# 10_-LPDDR4_SDRAM-2.net
KiCad netlist of a schematic drawn in Altium Designer
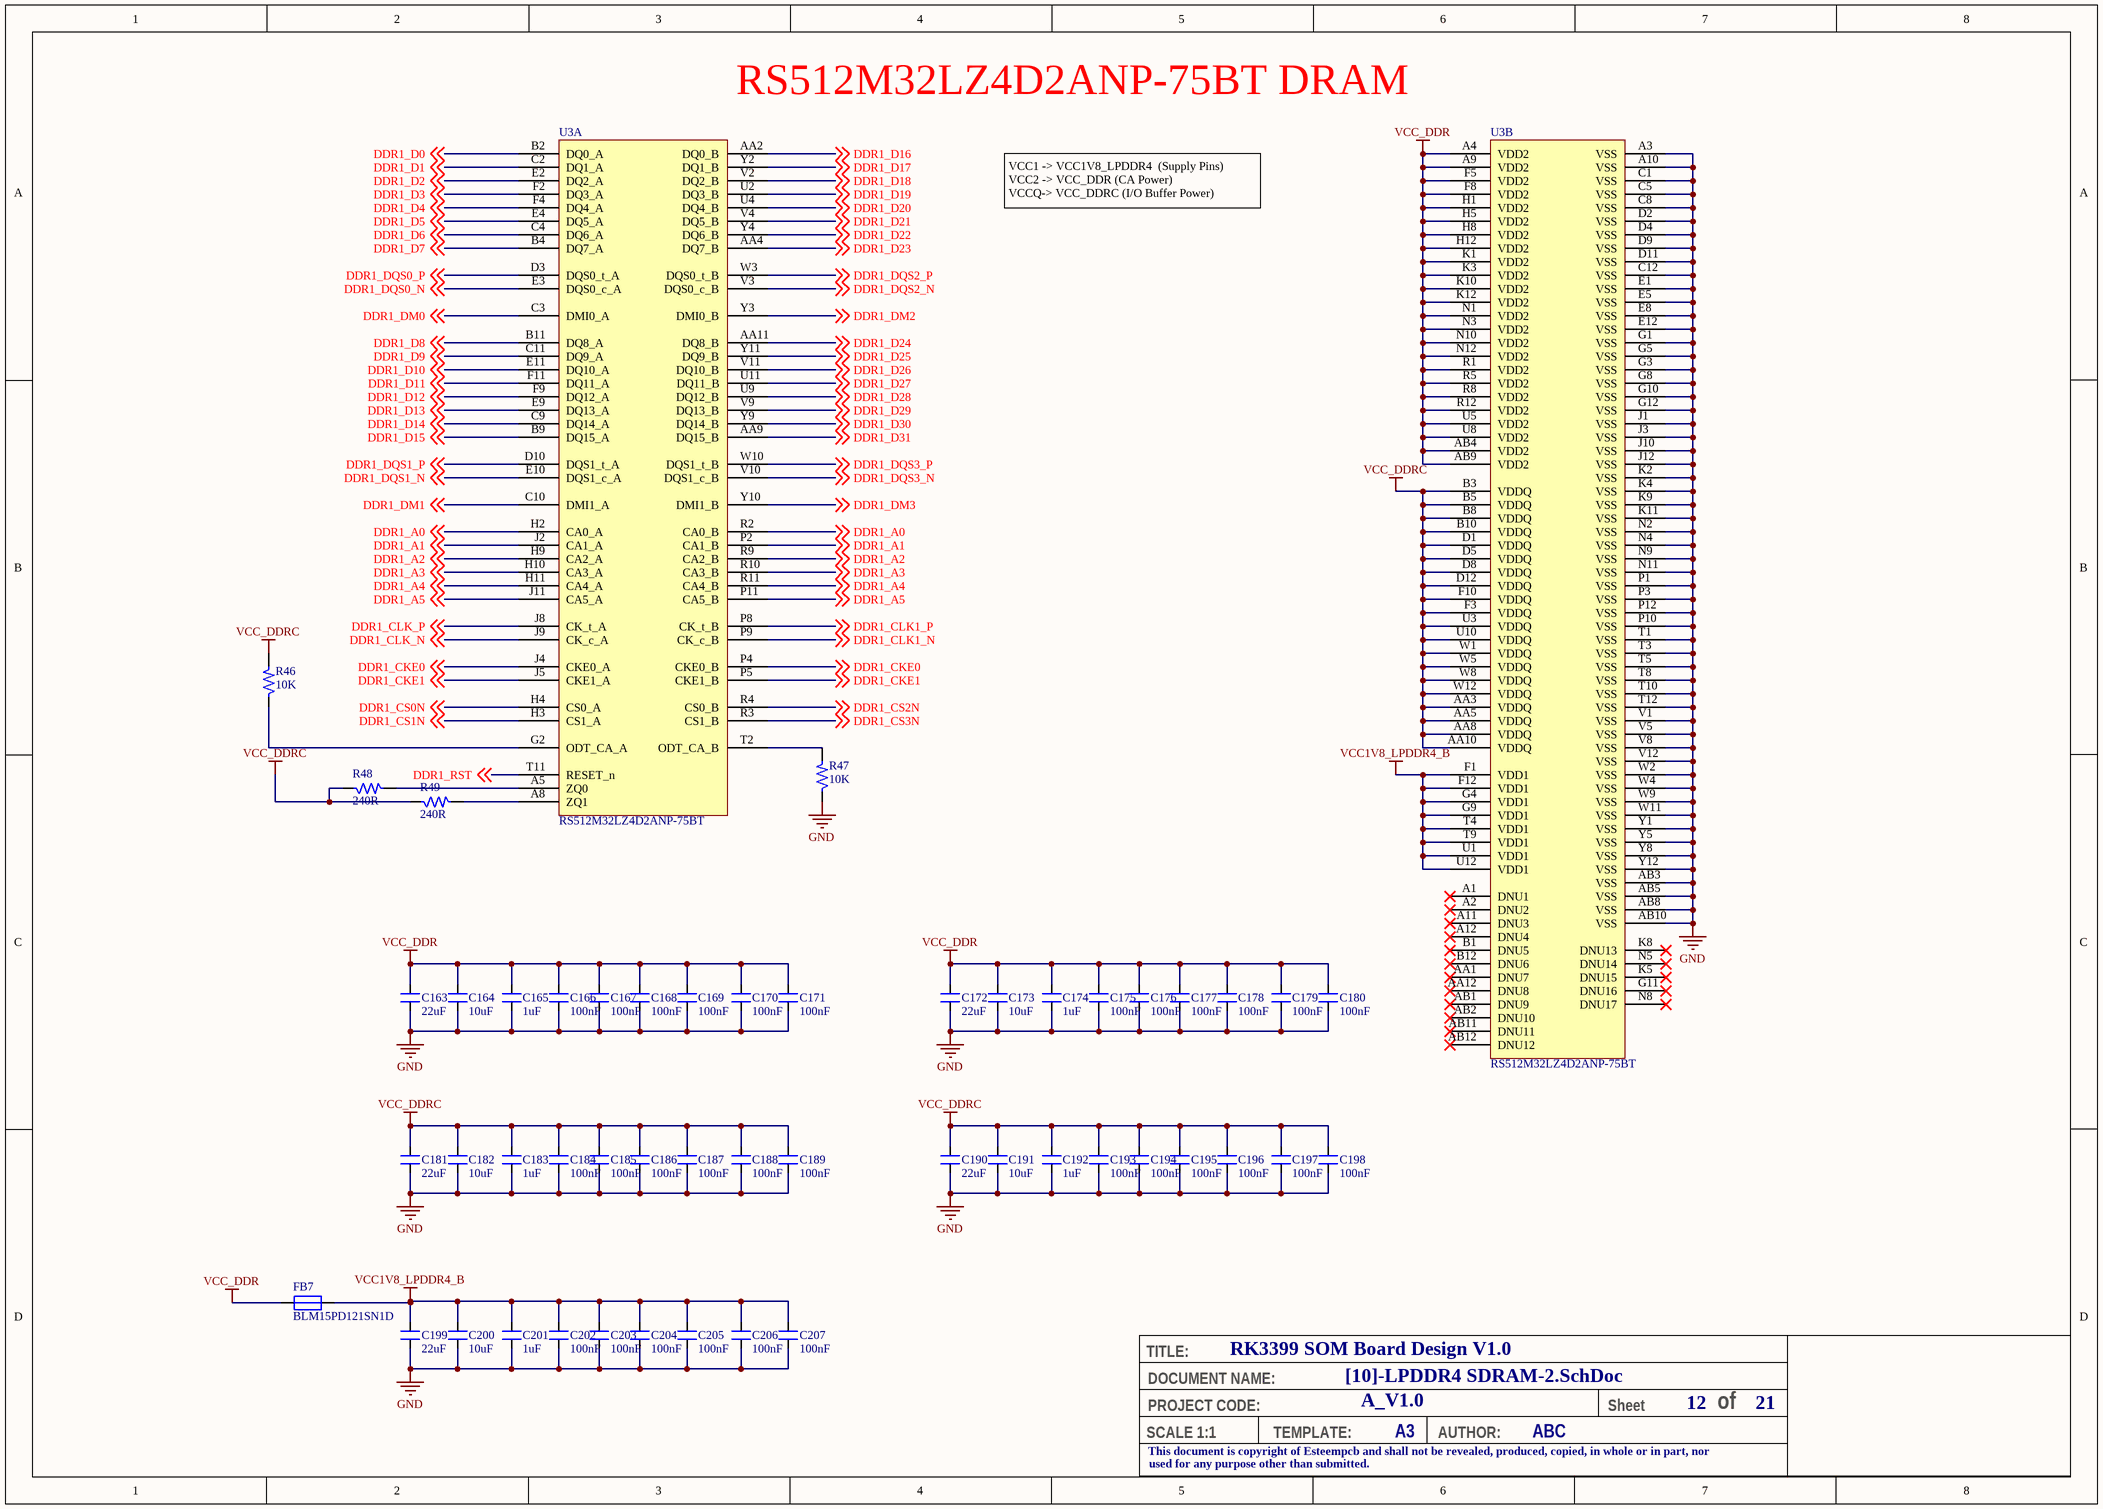
[diagram p0: [10]-LPDDR4 SDRAM-2.SchDoc]

(export (version "E")
  (design (tool "Eeschema 10.0.6"))
  (components
    (comp (ref "C163")
      (value "22uF")
      (footprint "CAP_0402")
      (description "22µF ±20% 6.3V Ceramic Capacitor X5R 0402 (1005 Metric)")
      (fields
        (field (name "MANUFACTURER") "Murata Electronics")
        (field (name "MANUFACTURER PART NUMBER") "CL05A226MQ5N6J8")
      )
      (libsource (lib "RK3399 _Module_Intlib") (part "CAP_22uF-6.3V-20%-0402"))
    )
    (comp (ref "C164")
      (value "10uF")
      (footprint "CAP_0402")
      (description "10µF ±20% 10V Ceramic Capacitor X5R 0402 (1005 Metric)")
      (fields
        (field (name "MANUFACTURER PART NUMBER") "CL05A106MP5NUNC")
        (field (name "MANUFACTURER") "Samsung Electro-Mechanics")
      )
      (libsource (lib "RK3399 _Module_Schlib") (part "CAP_10uF-10V-20%-0402"))
    )
    (comp (ref "C165")
      (value "1uF")
      (footprint "CAP_0201")
      (description "1µF ±20% 16V Ceramic Capacitor X5R 0201 (0603 Metric)")
      (fields
        (field (name "MANUFACTURER") "Samsung Electro-Mechanics")
        (field (name "MANUFACTURER PART NUMBER") "CL03A105MO3NRNH")
      )
      (libsource (lib "RK3399 _Module_Intlib") (part "CAP_1uF-16V-10%-0201"))
    )
    (comp (ref "C166")
      (value "100nF")
      (footprint "CAP_0201")
      (description "0.1µF ±10% 25V Ceramic Capacitor X5R 0201 (0603 Metric)")
      (fields
        (field (name "MANUFACTURER") "TDK Corporation")
        (field (name "MANUFACTURER PART NUMBER") "C0603X5R1E104K030BB")
      )
      (libsource (lib "RK3399 _Module_Intlib") (part "CAP_100nF-25V-10%-0201"))
    )
    (comp (ref "C167")
      (value "100nF")
      (footprint "CAP_0201")
      (description "0.1µF ±10% 25V Ceramic Capacitor X5R 0201 (0603 Metric)")
      (fields
        (field (name "MANUFACTURER") "TDK Corporation")
        (field (name "MANUFACTURER PART NUMBER") "C0603X5R1E104K030BB")
      )
      (libsource (lib "RK3399 _Module_Intlib") (part "CAP_100nF-25V-10%-0201"))
    )
    (comp (ref "C168")
      (value "100nF")
      (footprint "CAP_0201")
      (description "0.1µF ±10% 25V Ceramic Capacitor X5R 0201 (0603 Metric)")
      (fields
        (field (name "MANUFACTURER") "TDK Corporation")
        (field (name "MANUFACTURER PART NUMBER") "C0603X5R1E104K030BB")
      )
      (libsource (lib "RK3399 _Module_Intlib") (part "CAP_100nF-25V-10%-0201"))
    )
    (comp (ref "C169")
      (value "100nF")
      (footprint "CAP_0201")
      (description "0.1µF ±10% 25V Ceramic Capacitor X5R 0201 (0603 Metric)")
      (fields
        (field (name "MANUFACTURER") "TDK Corporation")
        (field (name "MANUFACTURER PART NUMBER") "C0603X5R1E104K030BB")
      )
      (libsource (lib "RK3399 _Module_Intlib") (part "CAP_100nF-25V-10%-0201"))
    )
    (comp (ref "C170")
      (value "100nF")
      (footprint "CAP_0201")
      (description "0.1µF ±10% 25V Ceramic Capacitor X5R 0201 (0603 Metric)")
      (fields
        (field (name "MANUFACTURER") "TDK Corporation")
        (field (name "MANUFACTURER PART NUMBER") "C0603X5R1E104K030BB")
      )
      (libsource (lib "RK3399 _Module_Intlib") (part "CAP_100nF-25V-10%-0201"))
    )
    (comp (ref "C171")
      (value "100nF")
      (footprint "CAP_0201")
      (description "0.1µF ±10% 25V Ceramic Capacitor X5R 0201 (0603 Metric)")
      (fields
        (field (name "MANUFACTURER") "TDK Corporation")
        (field (name "MANUFACTURER PART NUMBER") "C0603X5R1E104K030BB")
      )
      (libsource (lib "RK3399 _Module_Intlib") (part "CAP_100nF-25V-10%-0201"))
    )
    (comp (ref "C172")
      (value "22uF")
      (footprint "CAP_0402")
      (description "22µF ±20% 6.3V Ceramic Capacitor X5R 0402 (1005 Metric)")
      (fields
        (field (name "MANUFACTURER") "Murata Electronics")
        (field (name "MANUFACTURER PART NUMBER") "CL05A226MQ5N6J8")
      )
      (libsource (lib "RK3399 _Module_Intlib") (part "CAP_22uF-6.3V-20%-0402"))
    )
    (comp (ref "C173")
      (value "10uF")
      (footprint "CAP_0402")
      (description "10µF ±20% 10V Ceramic Capacitor X5R 0402 (1005 Metric)")
      (fields
        (field (name "MANUFACTURER PART NUMBER") "CL05A106MP5NUNC")
        (field (name "MANUFACTURER") "Samsung Electro-Mechanics")
      )
      (libsource (lib "RK3399 _Module_Schlib") (part "CAP_10uF-10V-20%-0402"))
    )
    (comp (ref "C174")
      (value "1uF")
      (footprint "CAP_0201")
      (description "1µF ±20% 16V Ceramic Capacitor X5R 0201 (0603 Metric)")
      (fields
        (field (name "MANUFACTURER") "Samsung Electro-Mechanics")
        (field (name "MANUFACTURER PART NUMBER") "CL03A105MO3NRNH")
      )
      (libsource (lib "RK3399 _Module_Intlib") (part "CAP_1uF-16V-10%-0201"))
    )
    (comp (ref "C175")
      (value "100nF")
      (footprint "CAP_0201")
      (description "0.1µF ±10% 25V Ceramic Capacitor X5R 0201 (0603 Metric)")
      (fields
        (field (name "MANUFACTURER") "TDK Corporation")
        (field (name "MANUFACTURER PART NUMBER") "C0603X5R1E104K030BB")
      )
      (libsource (lib "RK3399 _Module_Intlib") (part "CAP_100nF-25V-10%-0201"))
    )
    (comp (ref "C176")
      (value "100nF")
      (footprint "CAP_0201")
      (description "0.1µF ±10% 25V Ceramic Capacitor X5R 0201 (0603 Metric)")
      (fields
        (field (name "MANUFACTURER") "TDK Corporation")
        (field (name "MANUFACTURER PART NUMBER") "C0603X5R1E104K030BB")
      )
      (libsource (lib "RK3399 _Module_Intlib") (part "CAP_100nF-25V-10%-0201"))
    )
    (comp (ref "C177")
      (value "100nF")
      (footprint "CAP_0201")
      (description "0.1µF ±10% 25V Ceramic Capacitor X5R 0201 (0603 Metric)")
      (fields
        (field (name "MANUFACTURER") "TDK Corporation")
        (field (name "MANUFACTURER PART NUMBER") "C0603X5R1E104K030BB")
      )
      (libsource (lib "RK3399 _Module_Intlib") (part "CAP_100nF-25V-10%-0201"))
    )
    (comp (ref "C178")
      (value "100nF")
      (footprint "CAP_0201")
      (description "0.1µF ±10% 25V Ceramic Capacitor X5R 0201 (0603 Metric)")
      (fields
        (field (name "MANUFACTURER") "TDK Corporation")
        (field (name "MANUFACTURER PART NUMBER") "C0603X5R1E104K030BB")
      )
      (libsource (lib "RK3399 _Module_Intlib") (part "CAP_100nF-25V-10%-0201"))
    )
    (comp (ref "C179")
      (value "100nF")
      (footprint "CAP_0201")
      (description "0.1µF ±10% 25V Ceramic Capacitor X5R 0201 (0603 Metric)")
      (fields
        (field (name "MANUFACTURER") "TDK Corporation")
        (field (name "MANUFACTURER PART NUMBER") "C0603X5R1E104K030BB")
      )
      (libsource (lib "RK3399 _Module_Intlib") (part "CAP_100nF-25V-10%-0201"))
    )
    (comp (ref "C180")
      (value "100nF")
      (footprint "CAP_0201")
      (description "0.1µF ±10% 25V Ceramic Capacitor X5R 0201 (0603 Metric)")
      (fields
        (field (name "MANUFACTURER") "TDK Corporation")
        (field (name "MANUFACTURER PART NUMBER") "C0603X5R1E104K030BB")
      )
      (libsource (lib "RK3399 _Module_Intlib") (part "CAP_100nF-25V-10%-0201"))
    )
    (comp (ref "C181")
      (value "22uF")
      (footprint "CAP_0402")
      (description "22µF ±20% 6.3V Ceramic Capacitor X5R 0402 (1005 Metric)")
      (fields
        (field (name "MANUFACTURER") "Murata Electronics")
        (field (name "MANUFACTURER PART NUMBER") "CL05A226MQ5N6J8")
      )
      (libsource (lib "RK3399 _Module_Intlib") (part "CAP_22uF-6.3V-20%-0402"))
    )
    (comp (ref "C182")
      (value "10uF")
      (footprint "CAP_0402")
      (description "10µF ±20% 10V Ceramic Capacitor X5R 0402 (1005 Metric)")
      (fields
        (field (name "MANUFACTURER PART NUMBER") "CL05A106MP5NUNC")
        (field (name "MANUFACTURER") "Samsung Electro-Mechanics")
      )
      (libsource (lib "RK3399 _Module_Schlib") (part "CAP_10uF-10V-20%-0402"))
    )
    (comp (ref "C183")
      (value "1uF")
      (footprint "CAP_0201")
      (description "1µF ±20% 16V Ceramic Capacitor X5R 0201 (0603 Metric)")
      (fields
        (field (name "MANUFACTURER") "Samsung Electro-Mechanics")
        (field (name "MANUFACTURER PART NUMBER") "CL03A105MO3NRNH")
      )
      (libsource (lib "RK3399 _Module_Intlib") (part "CAP_1uF-16V-10%-0201"))
    )
    (comp (ref "C184")
      (value "100nF")
      (footprint "CAP_0201")
      (description "0.1µF ±10% 25V Ceramic Capacitor X5R 0201 (0603 Metric)")
      (fields
        (field (name "MANUFACTURER") "TDK Corporation")
        (field (name "MANUFACTURER PART NUMBER") "C0603X5R1E104K030BB")
      )
      (libsource (lib "RK3399 _Module_Intlib") (part "CAP_100nF-25V-10%-0201"))
    )
    (comp (ref "C185")
      (value "100nF")
      (footprint "CAP_0201")
      (description "0.1µF ±10% 25V Ceramic Capacitor X5R 0201 (0603 Metric)")
      (fields
        (field (name "MANUFACTURER") "TDK Corporation")
        (field (name "MANUFACTURER PART NUMBER") "C0603X5R1E104K030BB")
      )
      (libsource (lib "RK3399 _Module_Intlib") (part "CAP_100nF-25V-10%-0201"))
    )
    (comp (ref "C186")
      (value "100nF")
      (footprint "CAP_0201")
      (description "0.1µF ±10% 25V Ceramic Capacitor X5R 0201 (0603 Metric)")
      (fields
        (field (name "MANUFACTURER") "TDK Corporation")
        (field (name "MANUFACTURER PART NUMBER") "C0603X5R1E104K030BB")
      )
      (libsource (lib "RK3399 _Module_Intlib") (part "CAP_100nF-25V-10%-0201"))
    )
    (comp (ref "C187")
      (value "100nF")
      (footprint "CAP_0201")
      (description "0.1µF ±10% 25V Ceramic Capacitor X5R 0201 (0603 Metric)")
      (fields
        (field (name "MANUFACTURER") "TDK Corporation")
        (field (name "MANUFACTURER PART NUMBER") "C0603X5R1E104K030BB")
      )
      (libsource (lib "RK3399 _Module_Intlib") (part "CAP_100nF-25V-10%-0201"))
    )
    (comp (ref "C188")
      (value "100nF")
      (footprint "CAP_0201")
      (description "0.1µF ±10% 25V Ceramic Capacitor X5R 0201 (0603 Metric)")
      (fields
        (field (name "MANUFACTURER") "TDK Corporation")
        (field (name "MANUFACTURER PART NUMBER") "C0603X5R1E104K030BB")
      )
      (libsource (lib "RK3399 _Module_Intlib") (part "CAP_100nF-25V-10%-0201"))
    )
    (comp (ref "C189")
      (value "100nF")
      (footprint "CAP_0201")
      (description "0.1µF ±10% 25V Ceramic Capacitor X5R 0201 (0603 Metric)")
      (fields
        (field (name "MANUFACTURER") "TDK Corporation")
        (field (name "MANUFACTURER PART NUMBER") "C0603X5R1E104K030BB")
      )
      (libsource (lib "RK3399 _Module_Intlib") (part "CAP_100nF-25V-10%-0201"))
    )
    (comp (ref "C190")
      (value "22uF")
      (footprint "CAP_0402")
      (description "22µF ±20% 6.3V Ceramic Capacitor X5R 0402 (1005 Metric)")
      (fields
        (field (name "MANUFACTURER") "Murata Electronics")
        (field (name "MANUFACTURER PART NUMBER") "CL05A226MQ5N6J8")
      )
      (libsource (lib "RK3399 _Module_Intlib") (part "CAP_22uF-6.3V-20%-0402"))
    )
    (comp (ref "C191")
      (value "10uF")
      (footprint "CAP_0402")
      (description "10µF ±20% 10V Ceramic Capacitor X5R 0402 (1005 Metric)")
      (fields
        (field (name "MANUFACTURER PART NUMBER") "CL05A106MP5NUNC")
        (field (name "MANUFACTURER") "Samsung Electro-Mechanics")
      )
      (libsource (lib "RK3399 _Module_Schlib") (part "CAP_10uF-10V-20%-0402"))
    )
    (comp (ref "C192")
      (value "1uF")
      (footprint "CAP_0201")
      (description "1µF ±20% 16V Ceramic Capacitor X5R 0201 (0603 Metric)")
      (fields
        (field (name "MANUFACTURER") "Samsung Electro-Mechanics")
        (field (name "MANUFACTURER PART NUMBER") "CL03A105MO3NRNH")
      )
      (libsource (lib "RK3399 _Module_Intlib") (part "CAP_1uF-16V-10%-0201"))
    )
    (comp (ref "C193")
      (value "100nF")
      (footprint "CAP_0201")
      (description "0.1µF ±10% 25V Ceramic Capacitor X5R 0201 (0603 Metric)")
      (fields
        (field (name "MANUFACTURER") "TDK Corporation")
        (field (name "MANUFACTURER PART NUMBER") "C0603X5R1E104K030BB")
      )
      (libsource (lib "RK3399 _Module_Intlib") (part "CAP_100nF-25V-10%-0201"))
    )
    (comp (ref "C194")
      (value "100nF")
      (footprint "CAP_0201")
      (description "0.1µF ±10% 25V Ceramic Capacitor X5R 0201 (0603 Metric)")
      (fields
        (field (name "MANUFACTURER") "TDK Corporation")
        (field (name "MANUFACTURER PART NUMBER") "C0603X5R1E104K030BB")
      )
      (libsource (lib "RK3399 _Module_Intlib") (part "CAP_100nF-25V-10%-0201"))
    )
    (comp (ref "C195")
      (value "100nF")
      (footprint "CAP_0201")
      (description "0.1µF ±10% 25V Ceramic Capacitor X5R 0201 (0603 Metric)")
      (fields
        (field (name "MANUFACTURER") "TDK Corporation")
        (field (name "MANUFACTURER PART NUMBER") "C0603X5R1E104K030BB")
      )
      (libsource (lib "RK3399 _Module_Intlib") (part "CAP_100nF-25V-10%-0201"))
    )
    (comp (ref "C196")
      (value "100nF")
      (footprint "CAP_0201")
      (description "0.1µF ±10% 25V Ceramic Capacitor X5R 0201 (0603 Metric)")
      (fields
        (field (name "MANUFACTURER") "TDK Corporation")
        (field (name "MANUFACTURER PART NUMBER") "C0603X5R1E104K030BB")
      )
      (libsource (lib "RK3399 _Module_Intlib") (part "CAP_100nF-25V-10%-0201"))
    )
    (comp (ref "C197")
      (value "100nF")
      (footprint "CAP_0201")
      (description "0.1µF ±10% 25V Ceramic Capacitor X5R 0201 (0603 Metric)")
      (fields
        (field (name "MANUFACTURER") "TDK Corporation")
        (field (name "MANUFACTURER PART NUMBER") "C0603X5R1E104K030BB")
      )
      (libsource (lib "RK3399 _Module_Intlib") (part "CAP_100nF-25V-10%-0201"))
    )
    (comp (ref "C198")
      (value "100nF")
      (footprint "CAP_0201")
      (description "0.1µF ±10% 25V Ceramic Capacitor X5R 0201 (0603 Metric)")
      (fields
        (field (name "MANUFACTURER") "TDK Corporation")
        (field (name "MANUFACTURER PART NUMBER") "C0603X5R1E104K030BB")
      )
      (libsource (lib "RK3399 _Module_Intlib") (part "CAP_100nF-25V-10%-0201"))
    )
    (comp (ref "C199")
      (value "22uF")
      (footprint "CAP_0402")
      (description "22µF ±20% 6.3V Ceramic Capacitor X5R 0402 (1005 Metric)")
      (fields
        (field (name "MANUFACTURER") "Murata Electronics")
        (field (name "MANUFACTURER PART NUMBER") "CL05A226MQ5N6J8")
      )
      (libsource (lib "RK3399 _Module_Intlib") (part "CAP_22uF-6.3V-20%-0402"))
    )
    (comp (ref "C200")
      (value "10uF")
      (footprint "CAP_0402")
      (description "10µF ±20% 10V Ceramic Capacitor X5R 0402 (1005 Metric)")
      (fields
        (field (name "MANUFACTURER PART NUMBER") "CL05A106MP5NUNC")
        (field (name "MANUFACTURER") "Samsung Electro-Mechanics")
      )
      (libsource (lib "RK3399 _Module_Schlib") (part "CAP_10uF-10V-20%-0402"))
    )
    (comp (ref "C201")
      (value "1uF")
      (footprint "CAP_0201")
      (description "1µF ±20% 16V Ceramic Capacitor X5R 0201 (0603 Metric)")
      (fields
        (field (name "MANUFACTURER") "Samsung Electro-Mechanics")
        (field (name "MANUFACTURER PART NUMBER") "CL03A105MO3NRNH")
      )
      (libsource (lib "RK3399 _Module_Intlib") (part "CAP_1uF-16V-10%-0201"))
    )
    (comp (ref "C202")
      (value "100nF")
      (footprint "CAP_0201")
      (description "0.1µF ±10% 25V Ceramic Capacitor X5R 0201 (0603 Metric)")
      (fields
        (field (name "MANUFACTURER") "TDK Corporation")
        (field (name "MANUFACTURER PART NUMBER") "C0603X5R1E104K030BB")
      )
      (libsource (lib "RK3399 _Module_Intlib") (part "CAP_100nF-25V-10%-0201"))
    )
    (comp (ref "C203")
      (value "100nF")
      (footprint "CAP_0201")
      (description "0.1µF ±10% 25V Ceramic Capacitor X5R 0201 (0603 Metric)")
      (fields
        (field (name "MANUFACTURER") "TDK Corporation")
        (field (name "MANUFACTURER PART NUMBER") "C0603X5R1E104K030BB")
      )
      (libsource (lib "RK3399 _Module_Intlib") (part "CAP_100nF-25V-10%-0201"))
    )
    (comp (ref "C204")
      (value "100nF")
      (footprint "CAP_0201")
      (description "0.1µF ±10% 25V Ceramic Capacitor X5R 0201 (0603 Metric)")
      (fields
        (field (name "MANUFACTURER") "TDK Corporation")
        (field (name "MANUFACTURER PART NUMBER") "C0603X5R1E104K030BB")
      )
      (libsource (lib "RK3399 _Module_Intlib") (part "CAP_100nF-25V-10%-0201"))
    )
    (comp (ref "C205")
      (value "100nF")
      (footprint "CAP_0201")
      (description "0.1µF ±10% 25V Ceramic Capacitor X5R 0201 (0603 Metric)")
      (fields
        (field (name "MANUFACTURER") "TDK Corporation")
        (field (name "MANUFACTURER PART NUMBER") "C0603X5R1E104K030BB")
      )
      (libsource (lib "RK3399 _Module_Intlib") (part "CAP_100nF-25V-10%-0201"))
    )
    (comp (ref "C206")
      (value "100nF")
      (footprint "CAP_0201")
      (description "0.1µF ±10% 25V Ceramic Capacitor X5R 0201 (0603 Metric)")
      (fields
        (field (name "MANUFACTURER") "TDK Corporation")
        (field (name "MANUFACTURER PART NUMBER") "C0603X5R1E104K030BB")
      )
      (libsource (lib "RK3399 _Module_Intlib") (part "CAP_100nF-25V-10%-0201"))
    )
    (comp (ref "C207")
      (value "100nF")
      (footprint "CAP_0201")
      (description "0.1µF ±10% 25V Ceramic Capacitor X5R 0201 (0603 Metric)")
      (fields
        (field (name "MANUFACTURER") "TDK Corporation")
        (field (name "MANUFACTURER PART NUMBER") "C0603X5R1E104K030BB")
      )
      (libsource (lib "RK3399 _Module_Intlib") (part "CAP_100nF-25V-10%-0201"))
    )
    (comp (ref "FB7")
      (value "BLM15PD121SN1D")
      (footprint "RES_0402")
      (description "120 Ohms @ 100MHz 1 Power Line Ferrite Bead 0402 (1005 Metric) 1.3A 90mOhm")
      (fields (field (name "MANUFACTURER") "Murata Electronics"))
      (libsource (lib "RK3399 _Module_Schlib") (part "FB_120R-1.3A-100Mhz-0402"))
    )
    (comp (ref "R46")
      (value "10K")
      (footprint "RES_0201")
      (description "10 kOhms ±1% 0.05W, 1/20W Chip Resistor 0201 (0603 Metric) Thick Film")
      (fields
        (field (name "MANUFACTURER") "Stackpole Electronics Inc")
        (field (name "MANUFACTURER PART NUMBER") "RMCF0201FT10K0")
      )
      (libsource (lib "RK3399 _Module_Intlib") (part "RES_10K-0.05W-1%-0201"))
    )
    (comp (ref "R47")
      (value "10K")
      (footprint "RES_0201")
      (description "10 kOhms ±1% 0.05W, 1/20W Chip Resistor 0201 (0603 Metric) Thick Film")
      (fields
        (field (name "MANUFACTURER") "Stackpole Electronics Inc")
        (field (name "MANUFACTURER PART NUMBER") "RMCF0201FT10K0")
      )
      (libsource (lib "RK3399 _Module_Intlib") (part "RES_10K-0.05W-1%-0201"))
    )
    (comp (ref "R48")
      (value "240R")
      (footprint "RES_0201")
      (description "240 Ohms ±1% 0.05W, 1/20W Chip Resistor 0201 (0603 Metric) Thick Film")
      (fields
        (field (name "MANUFACTURER") "Yageo")
        (field (name "MANUFACTURER PART NUMBER") "RC0201FR-07240RL")
      )
      (libsource (lib "RK3399 _Module_Intlib") (part "RES_240R-0.05W-1%-0201"))
    )
    (comp (ref "R49")
      (value "240R")
      (footprint "RES_0201")
      (description "240 Ohms ±1% 0.05W, 1/20W Chip Resistor 0201 (0603 Metric) Thick Film")
      (fields
        (field (name "MANUFACTURER") "Yageo")
        (field (name "MANUFACTURER PART NUMBER") "RC0201FR-07240RL")
      )
      (libsource (lib "RK3399 _Module_Intlib") (part "RES_240R-0.05W-1%-0201"))
    )
    (comp (ref "U3")
      (value "RS512M32LZ4D2ANP-75BT")
      (footprint "FBGA200_SMD")
      (fields (field (name "MANUFACTURER") "RAYSON"))
      (libsource (lib "RK3399 _Module_Schlib") (part "IC_RS512M32LZ4D2ANP-75BT"))
    )
  )
  (nets
    (net (code "1") (name "DDR1_A0") (class "Default")
      (node (ref "U3") (pin "H2") (pinfunction "CA0_A_H2") (pintype "passive"))
      (node (ref "U3") (pin "R2") (pinfunction "CA0_B_R2") (pintype "passive"))
    )
    (net (code "2") (name "DDR1_A1") (class "Default")
      (node (ref "U3") (pin "J2") (pinfunction "CA1_A_J2") (pintype "passive"))
      (node (ref "U3") (pin "P2") (pinfunction "CA1_B_P2") (pintype "passive"))
    )
    (net (code "3") (name "DDR1_A2") (class "Default")
      (node (ref "U3") (pin "H9") (pinfunction "CA2_A_H9") (pintype "passive"))
      (node (ref "U3") (pin "R9") (pinfunction "CA2_B_R9") (pintype "passive"))
    )
    (net (code "4") (name "DDR1_A3") (class "Default")
      (node (ref "U3") (pin "H10") (pinfunction "CA3_A_H10") (pintype "passive"))
      (node (ref "U3") (pin "R10") (pinfunction "CA3_B_R10") (pintype "passive"))
    )
    (net (code "5") (name "DDR1_A4") (class "Default")
      (node (ref "U3") (pin "H11") (pinfunction "CA4_A_H11") (pintype "passive"))
      (node (ref "U3") (pin "R11") (pinfunction "CA4_B_R11") (pintype "passive"))
    )
    (net (code "6") (name "DDR1_A5") (class "Default")
      (node (ref "U3") (pin "J11") (pinfunction "CA5_A_J11") (pintype "passive"))
      (node (ref "U3") (pin "P11") (pinfunction "CA5_B_P11") (pintype "passive"))
    )
    (net (code "7") (name "DDR1_CKE0") (class "Default")
      (node (ref "U3") (pin "J4") (pinfunction "CKE0_A_J4") (pintype "passive"))
      (node (ref "U3") (pin "P4") (pinfunction "CKE0_B_P4") (pintype "passive"))
    )
    (net (code "8") (name "DDR1_CKE1") (class "Default")
      (node (ref "U3") (pin "J5") (pinfunction "CKE1_A_J5") (pintype "passive"))
      (node (ref "U3") (pin "P5") (pinfunction "CKE1_B_P5") (pintype "passive"))
    )
    (net (code "9") (name "DDR1_CLK1_N") (class "Default")
      (node (ref "U3") (pin "P9") (pinfunction "CK_c_B_P9") (pintype "passive"))
    )
    (net (code "10") (name "DDR1_CLK1_P") (class "Default")
      (node (ref "U3") (pin "P8") (pinfunction "CK_t_B_P8") (pintype "passive"))
    )
    (net (code "11") (name "DDR1_CLK_N") (class "Default")
      (node (ref "U3") (pin "J9") (pinfunction "CK_c_A_J9") (pintype "passive"))
    )
    (net (code "12") (name "DDR1_CLK_P") (class "Default")
      (node (ref "U3") (pin "J8") (pinfunction "CK_t_A_J8") (pintype "passive"))
    )
    (net (code "13") (name "DDR1_CS0N") (class "Default")
      (node (ref "U3") (pin "H4") (pinfunction "CS0_A_H4") (pintype "passive"))
    )
    (net (code "14") (name "DDR1_CS1N") (class "Default")
      (node (ref "U3") (pin "H3") (pinfunction "CS1_A_H3") (pintype "passive"))
    )
    (net (code "15") (name "DDR1_CS2N") (class "Default")
      (node (ref "U3") (pin "R4") (pinfunction "CS0_B_R4") (pintype "passive"))
    )
    (net (code "16") (name "DDR1_CS3N") (class "Default")
      (node (ref "U3") (pin "R3") (pinfunction "CS1_B_R3") (pintype "passive"))
    )
    (net (code "17") (name "DDR1_D0") (class "Default")
      (node (ref "U3") (pin "B2") (pinfunction "DQ0_A_B2") (pintype "passive"))
    )
    (net (code "18") (name "DDR1_D1") (class "Default")
      (node (ref "U3") (pin "C2") (pinfunction "DQ1_A_C2") (pintype "passive"))
    )
    (net (code "19") (name "DDR1_D2") (class "Default")
      (node (ref "U3") (pin "E2") (pinfunction "DQ2_A_E2") (pintype "passive"))
    )
    (net (code "20") (name "DDR1_D3") (class "Default")
      (node (ref "U3") (pin "F2") (pinfunction "DQ3_A_F2") (pintype "passive"))
    )
    (net (code "21") (name "DDR1_D4") (class "Default")
      (node (ref "U3") (pin "F4") (pinfunction "DQ4_A_F4") (pintype "passive"))
    )
    (net (code "22") (name "DDR1_D5") (class "Default")
      (node (ref "U3") (pin "E4") (pinfunction "DQ5_A_E4") (pintype "passive"))
    )
    (net (code "23") (name "DDR1_D6") (class "Default")
      (node (ref "U3") (pin "C4") (pinfunction "DQ6_A_C4") (pintype "passive"))
    )
    (net (code "24") (name "DDR1_D7") (class "Default")
      (node (ref "U3") (pin "B4") (pinfunction "DQ7_A_B4") (pintype "passive"))
    )
    (net (code "25") (name "DDR1_D8") (class "Default")
      (node (ref "U3") (pin "B11") (pinfunction "DQ8_A_B11") (pintype "passive"))
    )
    (net (code "26") (name "DDR1_D9") (class "Default")
      (node (ref "U3") (pin "C11") (pinfunction "DQ9_A_C11") (pintype "passive"))
    )
    (net (code "27") (name "DDR1_D10") (class "Default")
      (node (ref "U3") (pin "E11") (pinfunction "DQ10_A_E11") (pintype "passive"))
    )
    (net (code "28") (name "DDR1_D11") (class "Default")
      (node (ref "U3") (pin "F11") (pinfunction "DQ11_A_F11") (pintype "passive"))
    )
    (net (code "29") (name "DDR1_D12") (class "Default")
      (node (ref "U3") (pin "F9") (pinfunction "DQ12_A_F9") (pintype "passive"))
    )
    (net (code "30") (name "DDR1_D13") (class "Default")
      (node (ref "U3") (pin "E9") (pinfunction "DQ13_A_E9") (pintype "passive"))
    )
    (net (code "31") (name "DDR1_D14") (class "Default")
      (node (ref "U3") (pin "C9") (pinfunction "DQ14_A_C9") (pintype "passive"))
    )
    (net (code "32") (name "DDR1_D15") (class "Default")
      (node (ref "U3") (pin "B9") (pinfunction "DQ15_A_B9") (pintype "passive"))
    )
    (net (code "33") (name "DDR1_D16") (class "Default")
      (node (ref "U3") (pin "AA2") (pinfunction "DQ0_B_AA2") (pintype "passive"))
    )
    (net (code "34") (name "DDR1_D17") (class "Default")
      (node (ref "U3") (pin "Y2") (pinfunction "DQ1_B_Y2") (pintype "passive"))
    )
    (net (code "35") (name "DDR1_D18") (class "Default")
      (node (ref "U3") (pin "V2") (pinfunction "DQ2_B_V2") (pintype "passive"))
    )
    (net (code "36") (name "DDR1_D19") (class "Default")
      (node (ref "U3") (pin "U2") (pinfunction "DQ3_B_U2") (pintype "passive"))
    )
    (net (code "37") (name "DDR1_D20") (class "Default")
      (node (ref "U3") (pin "U4") (pinfunction "DQ4_B_U4") (pintype "passive"))
    )
    (net (code "38") (name "DDR1_D21") (class "Default")
      (node (ref "U3") (pin "V4") (pinfunction "DQ5_B_V4") (pintype "passive"))
    )
    (net (code "39") (name "DDR1_D22") (class "Default")
      (node (ref "U3") (pin "Y4") (pinfunction "DQ6_B_Y4") (pintype "passive"))
    )
    (net (code "40") (name "DDR1_D23") (class "Default")
      (node (ref "U3") (pin "AA4") (pinfunction "DQ7_B_AA4") (pintype "passive"))
    )
    (net (code "41") (name "DDR1_D24") (class "Default")
      (node (ref "U3") (pin "AA11") (pinfunction "DQ8_B_AA11") (pintype "passive"))
    )
    (net (code "42") (name "DDR1_D25") (class "Default")
      (node (ref "U3") (pin "Y11") (pinfunction "DQ9_B_Y11") (pintype "passive"))
    )
    (net (code "43") (name "DDR1_D26") (class "Default")
      (node (ref "U3") (pin "V11") (pinfunction "DQ10_B_V11") (pintype "passive"))
    )
    (net (code "44") (name "DDR1_D27") (class "Default")
      (node (ref "U3") (pin "U11") (pinfunction "DQ11_B_U11") (pintype "passive"))
    )
    (net (code "45") (name "DDR1_D28") (class "Default")
      (node (ref "U3") (pin "U9") (pinfunction "DQ12_B_U9") (pintype "passive"))
    )
    (net (code "46") (name "DDR1_D29") (class "Default")
      (node (ref "U3") (pin "V9") (pinfunction "DQ13_B_V9") (pintype "passive"))
    )
    (net (code "47") (name "DDR1_D30") (class "Default")
      (node (ref "U3") (pin "Y9") (pinfunction "DQ14_B_Y9") (pintype "passive"))
    )
    (net (code "48") (name "DDR1_D31") (class "Default")
      (node (ref "U3") (pin "AA9") (pinfunction "DQ15_B_AA9") (pintype "passive"))
    )
    (net (code "49") (name "DDR1_DM0") (class "Default")
      (node (ref "U3") (pin "C3") (pinfunction "DMI0_A_C3") (pintype "passive"))
    )
    (net (code "50") (name "DDR1_DM1") (class "Default")
      (node (ref "U3") (pin "C10") (pinfunction "DMI1_A_C10") (pintype "passive"))
    )
    (net (code "51") (name "DDR1_DM2") (class "Default")
      (node (ref "U3") (pin "Y3") (pinfunction "DMI0_B_Y3") (pintype "passive"))
    )
    (net (code "52") (name "DDR1_DM3") (class "Default")
      (node (ref "U3") (pin "Y10") (pinfunction "DMI1_B_Y10") (pintype "passive"))
    )
    (net (code "53") (name "DDR1_DQS0_N") (class "Default")
      (node (ref "U3") (pin "E3") (pinfunction "DQS0_c_A_E3") (pintype "passive"))
    )
    (net (code "54") (name "DDR1_DQS0_P") (class "Default")
      (node (ref "U3") (pin "D3") (pinfunction "DQS0_t_A_D3") (pintype "passive"))
    )
    (net (code "55") (name "DDR1_DQS1_N") (class "Default")
      (node (ref "U3") (pin "E10") (pinfunction "DQS1_c_A_E10") (pintype "passive"))
    )
    (net (code "56") (name "DDR1_DQS1_P") (class "Default")
      (node (ref "U3") (pin "D10") (pinfunction "DQS1_t_A_D10") (pintype "passive"))
    )
    (net (code "57") (name "DDR1_DQS2_N") (class "Default")
      (node (ref "U3") (pin "V3") (pinfunction "DQS0_c_B_V3") (pintype "passive"))
    )
    (net (code "58") (name "DDR1_DQS2_P") (class "Default")
      (node (ref "U3") (pin "W3") (pinfunction "DQS0_t_B_W3") (pintype "passive"))
    )
    (net (code "59") (name "DDR1_DQS3_N") (class "Default")
      (node (ref "U3") (pin "V10") (pinfunction "DQS1_c_B_V10") (pintype "passive"))
    )
    (net (code "60") (name "DDR1_DQS3_P") (class "Default")
      (node (ref "U3") (pin "W10") (pinfunction "DQS1_t_B_W10") (pintype "passive"))
    )
    (net (code "61") (name "DDR1_RST") (class "Default")
      (node (ref "U3") (pin "T11") (pinfunction "RESET_n_T11") (pintype "passive"))
    )
    (net (code "62") (name "GND") (class "Default")
      (node (ref "C163") (pin "1") (pinfunction "1_1") (pintype "passive"))
      (node (ref "C164") (pin "1") (pinfunction "1_1") (pintype "passive"))
      (node (ref "C165") (pin "1") (pinfunction "1_1") (pintype "passive"))
      (node (ref "C166") (pin "1") (pinfunction "1_1") (pintype "passive"))
      (node (ref "C167") (pin "1") (pinfunction "1_1") (pintype "passive"))
      (node (ref "C168") (pin "1") (pinfunction "1_1") (pintype "passive"))
      (node (ref "C169") (pin "1") (pinfunction "1_1") (pintype "passive"))
      (node (ref "C170") (pin "1") (pinfunction "1_1") (pintype "passive"))
      (node (ref "C171") (pin "1") (pinfunction "1_1") (pintype "passive"))
      (node (ref "C172") (pin "1") (pinfunction "1_1") (pintype "passive"))
      (node (ref "C173") (pin "1") (pinfunction "1_1") (pintype "passive"))
      (node (ref "C174") (pin "1") (pinfunction "1_1") (pintype "passive"))
      (node (ref "C175") (pin "1") (pinfunction "1_1") (pintype "passive"))
      (node (ref "C176") (pin "1") (pinfunction "1_1") (pintype "passive"))
      (node (ref "C177") (pin "1") (pinfunction "1_1") (pintype "passive"))
      (node (ref "C178") (pin "1") (pinfunction "1_1") (pintype "passive"))
      (node (ref "C179") (pin "1") (pinfunction "1_1") (pintype "passive"))
      (node (ref "C180") (pin "1") (pinfunction "1_1") (pintype "passive"))
      (node (ref "C181") (pin "1") (pinfunction "1_1") (pintype "passive"))
      (node (ref "C182") (pin "1") (pinfunction "1_1") (pintype "passive"))
      (node (ref "C183") (pin "1") (pinfunction "1_1") (pintype "passive"))
      (node (ref "C184") (pin "1") (pinfunction "1_1") (pintype "passive"))
      (node (ref "C185") (pin "1") (pinfunction "1_1") (pintype "passive"))
      (node (ref "C186") (pin "1") (pinfunction "1_1") (pintype "passive"))
      (node (ref "C187") (pin "1") (pinfunction "1_1") (pintype "passive"))
      (node (ref "C188") (pin "1") (pinfunction "1_1") (pintype "passive"))
      (node (ref "C189") (pin "1") (pinfunction "1_1") (pintype "passive"))
      (node (ref "C190") (pin "1") (pinfunction "1_1") (pintype "passive"))
      (node (ref "C191") (pin "1") (pinfunction "1_1") (pintype "passive"))
      (node (ref "C192") (pin "1") (pinfunction "1_1") (pintype "passive"))
      (node (ref "C193") (pin "1") (pinfunction "1_1") (pintype "passive"))
      (node (ref "C194") (pin "1") (pinfunction "1_1") (pintype "passive"))
      (node (ref "C195") (pin "1") (pinfunction "1_1") (pintype "passive"))
      (node (ref "C196") (pin "1") (pinfunction "1_1") (pintype "passive"))
      (node (ref "C197") (pin "1") (pinfunction "1_1") (pintype "passive"))
      (node (ref "C198") (pin "1") (pinfunction "1_1") (pintype "passive"))
      (node (ref "C199") (pin "1") (pinfunction "1_1") (pintype "passive"))
      (node (ref "C200") (pin "1") (pinfunction "1_1") (pintype "passive"))
      (node (ref "C201") (pin "1") (pinfunction "1_1") (pintype "passive"))
      (node (ref "C202") (pin "1") (pinfunction "1_1") (pintype "passive"))
      (node (ref "C203") (pin "1") (pinfunction "1_1") (pintype "passive"))
      (node (ref "C204") (pin "1") (pinfunction "1_1") (pintype "passive"))
      (node (ref "C205") (pin "1") (pinfunction "1_1") (pintype "passive"))
      (node (ref "C206") (pin "1") (pinfunction "1_1") (pintype "passive"))
      (node (ref "C207") (pin "1") (pinfunction "1_1") (pintype "passive"))
      (node (ref "R47") (pin "1") (pinfunction "1_1") (pintype "passive"))
      (node (ref "U3") (pin "A10") (pinfunction "VSS_A10") (pintype "passive"))
      (node (ref "U3") (pin "A3") (pinfunction "VSS_A3") (pintype "passive"))
      (node (ref "U3") (pin "AB10") (pinfunction "VSS_AB10") (pintype "passive"))
      (node (ref "U3") (pin "AB3") (pinfunction "VSS_AB3") (pintype "passive"))
      (node (ref "U3") (pin "AB5") (pinfunction "VSS_AB5") (pintype "passive"))
      (node (ref "U3") (pin "AB8") (pinfunction "VSS_AB8") (pintype "passive"))
      (node (ref "U3") (pin "C1") (pinfunction "VSS_C1") (pintype "passive"))
      (node (ref "U3") (pin "C12") (pinfunction "VSS_C12") (pintype "passive"))
      (node (ref "U3") (pin "C5") (pinfunction "VSS_C5") (pintype "passive"))
      (node (ref "U3") (pin "C8") (pinfunction "VSS_C8") (pintype "passive"))
      (node (ref "U3") (pin "D11") (pinfunction "VSS_D11") (pintype "passive"))
      (node (ref "U3") (pin "D2") (pinfunction "VSS_D2") (pintype "passive"))
      (node (ref "U3") (pin "D4") (pinfunction "VSS_D4") (pintype "passive"))
      (node (ref "U3") (pin "D9") (pinfunction "VSS_D9") (pintype "passive"))
      (node (ref "U3") (pin "E1") (pinfunction "VSS_E1") (pintype "passive"))
      (node (ref "U3") (pin "E12") (pinfunction "VSS_E12") (pintype "passive"))
      (node (ref "U3") (pin "E5") (pinfunction "VSS_E5") (pintype "passive"))
      (node (ref "U3") (pin "E8") (pinfunction "VSS_E8") (pintype "passive"))
      (node (ref "U3") (pin "G1") (pinfunction "VSS_G1") (pintype "passive"))
      (node (ref "U3") (pin "G10") (pinfunction "VSS_G10") (pintype "passive"))
      (node (ref "U3") (pin "G12") (pinfunction "VSS_G12") (pintype "passive"))
      (node (ref "U3") (pin "G3") (pinfunction "VSS_G3") (pintype "passive"))
      (node (ref "U3") (pin "G5") (pinfunction "VSS_G5") (pintype "passive"))
      (node (ref "U3") (pin "G8") (pinfunction "VSS_G8") (pintype "passive"))
      (node (ref "U3") (pin "J1") (pinfunction "VSS_J1") (pintype "passive"))
      (node (ref "U3") (pin "J10") (pinfunction "VSS_J10") (pintype "passive"))
      (node (ref "U3") (pin "J12") (pinfunction "VSS_J12") (pintype "passive"))
      (node (ref "U3") (pin "J3") (pinfunction "VSS_J3") (pintype "passive"))
      (node (ref "U3") (pin "K11") (pinfunction "VSS_K11") (pintype "passive"))
      (node (ref "U3") (pin "K2") (pinfunction "VSS_K2") (pintype "passive"))
      (node (ref "U3") (pin "K4") (pinfunction "VSS_K4") (pintype "passive"))
      (node (ref "U3") (pin "K9") (pinfunction "VSS_K9") (pintype "passive"))
      (node (ref "U3") (pin "N11") (pinfunction "VSS_N11") (pintype "passive"))
      (node (ref "U3") (pin "N2") (pinfunction "VSS_N2") (pintype "passive"))
      (node (ref "U3") (pin "N4") (pinfunction "VSS_N4") (pintype "passive"))
      (node (ref "U3") (pin "N9") (pinfunction "VSS_N9") (pintype "passive"))
      (node (ref "U3") (pin "P1") (pinfunction "VSS_P1") (pintype "passive"))
      (node (ref "U3") (pin "P10") (pinfunction "VSS_P10") (pintype "passive"))
      (node (ref "U3") (pin "P12") (pinfunction "VSS_P12") (pintype "passive"))
      (node (ref "U3") (pin "P3") (pinfunction "VSS_P3") (pintype "passive"))
      (node (ref "U3") (pin "T1") (pinfunction "VSS_T1") (pintype "passive"))
      (node (ref "U3") (pin "T10") (pinfunction "VSS_T10") (pintype "passive"))
      (node (ref "U3") (pin "T12") (pinfunction "VSS_T12") (pintype "passive"))
      (node (ref "U3") (pin "T3") (pinfunction "VSS_T3") (pintype "passive"))
      (node (ref "U3") (pin "T5") (pinfunction "VSS_T5") (pintype "passive"))
      (node (ref "U3") (pin "T8") (pinfunction "VSS_T8") (pintype "passive"))
      (node (ref "U3") (pin "V1") (pinfunction "VSS_V1") (pintype "passive"))
      (node (ref "U3") (pin "V12") (pinfunction "VSS_V12") (pintype "passive"))
      (node (ref "U3") (pin "V5") (pinfunction "VSS_V5") (pintype "passive"))
      (node (ref "U3") (pin "V8") (pinfunction "VSS_V8") (pintype "passive"))
      (node (ref "U3") (pin "W11") (pinfunction "VSS_W11") (pintype "passive"))
      (node (ref "U3") (pin "W2") (pinfunction "VSS_W2") (pintype "passive"))
      (node (ref "U3") (pin "W4") (pinfunction "VSS_W4") (pintype "passive"))
      (node (ref "U3") (pin "W9") (pinfunction "VSS_W9") (pintype "passive"))
      (node (ref "U3") (pin "Y1") (pinfunction "VSS_Y1") (pintype "passive"))
      (node (ref "U3") (pin "Y12") (pinfunction "VSS_Y12") (pintype "passive"))
      (node (ref "U3") (pin "Y5") (pinfunction "VSS_Y5") (pintype "passive"))
      (node (ref "U3") (pin "Y8") (pinfunction "VSS_Y8") (pintype "passive"))
    )
    (net (code "63") (name "Net-(U3A-ODT_CA_A)") (class "Default")
      (node (ref "R46") (pin "1") (pinfunction "1_1") (pintype "passive"))
      (node (ref "U3") (pin "G2") (pinfunction "ODT_CA_A_G2") (pintype "passive"))
    )
    (net (code "64") (name "Net-(U3A-ODT_CA_B)") (class "Default")
      (node (ref "R47") (pin "2") (pinfunction "2_2") (pintype "passive"))
      (node (ref "U3") (pin "T2") (pinfunction "ODT_CA_B_T2") (pintype "passive"))
    )
    (net (code "65") (name "Net-(U3A-ZQ0)") (class "Default")
      (node (ref "R48") (pin "2") (pinfunction "2_2") (pintype "passive"))
      (node (ref "U3") (pin "A5") (pinfunction "ZQ0_A5") (pintype "passive"))
    )
    (net (code "66") (name "Net-(U3A-ZQ1)") (class "Default")
      (node (ref "R49") (pin "2") (pinfunction "2_2") (pintype "passive"))
      (node (ref "U3") (pin "A8") (pinfunction "ZQ1_A8") (pintype "passive"))
    )
    (net (code "67") (name "VCC1V8_LPDDR4_B") (class "Default")
      (node (ref "C199") (pin "2") (pinfunction "2_2") (pintype "passive"))
      (node (ref "C200") (pin "2") (pinfunction "2_2") (pintype "passive"))
      (node (ref "C201") (pin "2") (pinfunction "2_2") (pintype "passive"))
      (node (ref "C202") (pin "2") (pinfunction "2_2") (pintype "passive"))
      (node (ref "C203") (pin "2") (pinfunction "2_2") (pintype "passive"))
      (node (ref "C204") (pin "2") (pinfunction "2_2") (pintype "passive"))
      (node (ref "C205") (pin "2") (pinfunction "2_2") (pintype "passive"))
      (node (ref "C206") (pin "2") (pinfunction "2_2") (pintype "passive"))
      (node (ref "C207") (pin "2") (pinfunction "2_2") (pintype "passive"))
      (node (ref "FB7") (pin "2") (pinfunction "2_2") (pintype "passive"))
      (node (ref "U3") (pin "F1") (pinfunction "VDD1_F1") (pintype "passive"))
      (node (ref "U3") (pin "F12") (pinfunction "VDD1_F12") (pintype "passive"))
      (node (ref "U3") (pin "G4") (pinfunction "VDD1_G4") (pintype "passive"))
      (node (ref "U3") (pin "G9") (pinfunction "VDD1_G9") (pintype "passive"))
      (node (ref "U3") (pin "T4") (pinfunction "VDD1_T4") (pintype "passive"))
      (node (ref "U3") (pin "T9") (pinfunction "VDD1_T9") (pintype "passive"))
      (node (ref "U3") (pin "U1") (pinfunction "VDD1_U1") (pintype "passive"))
      (node (ref "U3") (pin "U12") (pinfunction "VDD1_U12") (pintype "passive"))
    )
    (net (code "68") (name "VCC_DDR") (class "Default")
      (node (ref "C163") (pin "2") (pinfunction "2_2") (pintype "passive"))
      (node (ref "C164") (pin "2") (pinfunction "2_2") (pintype "passive"))
      (node (ref "C165") (pin "2") (pinfunction "2_2") (pintype "passive"))
      (node (ref "C166") (pin "2") (pinfunction "2_2") (pintype "passive"))
      (node (ref "C167") (pin "2") (pinfunction "2_2") (pintype "passive"))
      (node (ref "C168") (pin "2") (pinfunction "2_2") (pintype "passive"))
      (node (ref "C169") (pin "2") (pinfunction "2_2") (pintype "passive"))
      (node (ref "C170") (pin "2") (pinfunction "2_2") (pintype "passive"))
      (node (ref "C171") (pin "2") (pinfunction "2_2") (pintype "passive"))
      (node (ref "C172") (pin "2") (pinfunction "2_2") (pintype "passive"))
      (node (ref "C173") (pin "2") (pinfunction "2_2") (pintype "passive"))
      (node (ref "C174") (pin "2") (pinfunction "2_2") (pintype "passive"))
      (node (ref "C175") (pin "2") (pinfunction "2_2") (pintype "passive"))
      (node (ref "C176") (pin "2") (pinfunction "2_2") (pintype "passive"))
      (node (ref "C177") (pin "2") (pinfunction "2_2") (pintype "passive"))
      (node (ref "C178") (pin "2") (pinfunction "2_2") (pintype "passive"))
      (node (ref "C179") (pin "2") (pinfunction "2_2") (pintype "passive"))
      (node (ref "C180") (pin "2") (pinfunction "2_2") (pintype "passive"))
      (node (ref "FB7") (pin "1") (pinfunction "1_1") (pintype "passive"))
      (node (ref "U3") (pin "A4") (pinfunction "VDD2_A4") (pintype "passive"))
      (node (ref "U3") (pin "A9") (pinfunction "VDD2_A9") (pintype "passive"))
      (node (ref "U3") (pin "AB4") (pinfunction "VDD2_AB4") (pintype "passive"))
      (node (ref "U3") (pin "AB9") (pinfunction "VDD2_AB9") (pintype "passive"))
      (node (ref "U3") (pin "F5") (pinfunction "VDD2_F5") (pintype "passive"))
      (node (ref "U3") (pin "F8") (pinfunction "VDD2_F8") (pintype "passive"))
      (node (ref "U3") (pin "H1") (pinfunction "VDD2_H1") (pintype "passive"))
      (node (ref "U3") (pin "H12") (pinfunction "VDD2_H12") (pintype "passive"))
      (node (ref "U3") (pin "H5") (pinfunction "VDD2_H5") (pintype "passive"))
      (node (ref "U3") (pin "H8") (pinfunction "VDD2_H8") (pintype "passive"))
      (node (ref "U3") (pin "K1") (pinfunction "VDD2_K1") (pintype "passive"))
      (node (ref "U3") (pin "K10") (pinfunction "VDD2_K10") (pintype "passive"))
      (node (ref "U3") (pin "K12") (pinfunction "VDD2_K12") (pintype "passive"))
      (node (ref "U3") (pin "K3") (pinfunction "VDD2_K3") (pintype "passive"))
      (node (ref "U3") (pin "N1") (pinfunction "VDD2_N1") (pintype "passive"))
      (node (ref "U3") (pin "N10") (pinfunction "VDD2_N10") (pintype "passive"))
      (node (ref "U3") (pin "N12") (pinfunction "VDD2_N12") (pintype "passive"))
      (node (ref "U3") (pin "N3") (pinfunction "VDD2_N3") (pintype "passive"))
      (node (ref "U3") (pin "R1") (pinfunction "VDD2_R1") (pintype "passive"))
      (node (ref "U3") (pin "R12") (pinfunction "VDD2_R12") (pintype "passive"))
      (node (ref "U3") (pin "R5") (pinfunction "VDD2_R5") (pintype "passive"))
      (node (ref "U3") (pin "R8") (pinfunction "VDD2_R8") (pintype "passive"))
      (node (ref "U3") (pin "U5") (pinfunction "VDD2_U5") (pintype "passive"))
      (node (ref "U3") (pin "U8") (pinfunction "VDD2_U8") (pintype "passive"))
    )
    (net (code "69") (name "VCC_DDRC") (class "Default")
      (node (ref "C181") (pin "2") (pinfunction "2_2") (pintype "passive"))
      (node (ref "C182") (pin "2") (pinfunction "2_2") (pintype "passive"))
      (node (ref "C183") (pin "2") (pinfunction "2_2") (pintype "passive"))
      (node (ref "C184") (pin "2") (pinfunction "2_2") (pintype "passive"))
      (node (ref "C185") (pin "2") (pinfunction "2_2") (pintype "passive"))
      (node (ref "C186") (pin "2") (pinfunction "2_2") (pintype "passive"))
      (node (ref "C187") (pin "2") (pinfunction "2_2") (pintype "passive"))
      (node (ref "C188") (pin "2") (pinfunction "2_2") (pintype "passive"))
      (node (ref "C189") (pin "2") (pinfunction "2_2") (pintype "passive"))
      (node (ref "C190") (pin "2") (pinfunction "2_2") (pintype "passive"))
      (node (ref "C191") (pin "2") (pinfunction "2_2") (pintype "passive"))
      (node (ref "C192") (pin "2") (pinfunction "2_2") (pintype "passive"))
      (node (ref "C193") (pin "2") (pinfunction "2_2") (pintype "passive"))
      (node (ref "C194") (pin "2") (pinfunction "2_2") (pintype "passive"))
      (node (ref "C195") (pin "2") (pinfunction "2_2") (pintype "passive"))
      (node (ref "C196") (pin "2") (pinfunction "2_2") (pintype "passive"))
      (node (ref "C197") (pin "2") (pinfunction "2_2") (pintype "passive"))
      (node (ref "C198") (pin "2") (pinfunction "2_2") (pintype "passive"))
      (node (ref "R46") (pin "2") (pinfunction "2_2") (pintype "passive"))
      (node (ref "R48") (pin "1") (pinfunction "1_1") (pintype "passive"))
      (node (ref "R49") (pin "1") (pinfunction "1_1") (pintype "passive"))
      (node (ref "U3") (pin "AA10") (pinfunction "VDDQ_AA10") (pintype "passive"))
      (node (ref "U3") (pin "AA3") (pinfunction "VDDQ_AA3") (pintype "passive"))
      (node (ref "U3") (pin "AA5") (pinfunction "VDDQ_AA5") (pintype "passive"))
      (node (ref "U3") (pin "AA8") (pinfunction "VDDQ_AA8") (pintype "passive"))
      (node (ref "U3") (pin "B10") (pinfunction "VDDQ_B10") (pintype "passive"))
      (node (ref "U3") (pin "B3") (pinfunction "VDDQ_B3") (pintype "passive"))
      (node (ref "U3") (pin "B5") (pinfunction "VDDQ_B5") (pintype "passive"))
      (node (ref "U3") (pin "B8") (pinfunction "VDDQ_B8") (pintype "passive"))
      (node (ref "U3") (pin "D1") (pinfunction "VDDQ_D1") (pintype "passive"))
      (node (ref "U3") (pin "D12") (pinfunction "VDDQ_D12") (pintype "passive"))
      (node (ref "U3") (pin "D5") (pinfunction "VDDQ_D5") (pintype "passive"))
      (node (ref "U3") (pin "D8") (pinfunction "VDDQ_D8") (pintype "passive"))
      (node (ref "U3") (pin "F10") (pinfunction "VDDQ_F10") (pintype "passive"))
      (node (ref "U3") (pin "F3") (pinfunction "VDDQ_F3") (pintype "passive"))
      (node (ref "U3") (pin "U10") (pinfunction "VDDQ_U10") (pintype "passive"))
      (node (ref "U3") (pin "U3") (pinfunction "VDDQ_U3") (pintype "passive"))
      (node (ref "U3") (pin "W1") (pinfunction "VDDQ_W1") (pintype "passive"))
      (node (ref "U3") (pin "W12") (pinfunction "VDDQ_W12") (pintype "passive"))
      (node (ref "U3") (pin "W5") (pinfunction "VDDQ_W5") (pintype "passive"))
      (node (ref "U3") (pin "W8") (pinfunction "VDDQ_W8") (pintype "passive"))
    )
    (net (code "70") (name "unconnected-(U3B-DNU1-PadA1)") (class "Default")
      (node (ref "U3") (pin "A1") (pinfunction "DNU1_A1") (pintype "passive+no_connect"))
    )
    (net (code "71") (name "unconnected-(U3B-DNU2-PadA2)") (class "Default")
      (node (ref "U3") (pin "A2") (pinfunction "DNU2_A2") (pintype "passive+no_connect"))
    )
    (net (code "72") (name "unconnected-(U3B-DNU3-PadA11)") (class "Default")
      (node (ref "U3") (pin "A11") (pinfunction "DNU3_A11") (pintype "passive+no_connect"))
    )
    (net (code "73") (name "unconnected-(U3B-DNU4-PadA12)") (class "Default")
      (node (ref "U3") (pin "A12") (pinfunction "DNU4_A12") (pintype "passive+no_connect"))
    )
    (net (code "74") (name "unconnected-(U3B-DNU5-PadB1)") (class "Default")
      (node (ref "U3") (pin "B1") (pinfunction "DNU5_B1") (pintype "passive+no_connect"))
    )
    (net (code "75") (name "unconnected-(U3B-DNU6-PadB12)") (class "Default")
      (node (ref "U3") (pin "B12") (pinfunction "DNU6_B12") (pintype "passive+no_connect"))
    )
    (net (code "76") (name "unconnected-(U3B-DNU7-PadAA1)") (class "Default")
      (node (ref "U3") (pin "AA1") (pinfunction "DNU7_AA1") (pintype "passive+no_connect"))
    )
    (net (code "77") (name "unconnected-(U3B-DNU8-PadAA12)") (class "Default")
      (node (ref "U3") (pin "AA12") (pinfunction "DNU8_AA12") (pintype "passive+no_connect"))
    )
    (net (code "78") (name "unconnected-(U3B-DNU9-PadAB1)") (class "Default")
      (node (ref "U3") (pin "AB1") (pinfunction "DNU9_AB1") (pintype "passive+no_connect"))
    )
    (net (code "79") (name "unconnected-(U3B-DNU10-PadAB2)") (class "Default")
      (node (ref "U3") (pin "AB2") (pinfunction "DNU10_AB2") (pintype "passive+no_connect"))
    )
    (net (code "80") (name "unconnected-(U3B-DNU11-PadAB11)") (class "Default")
      (node (ref "U3") (pin "AB11") (pinfunction "DNU11_AB11") (pintype "passive+no_connect"))
    )
    (net (code "81") (name "unconnected-(U3B-DNU12-PadAB12)") (class "Default")
      (node (ref "U3") (pin "AB12") (pinfunction "DNU12_AB12") (pintype "passive+no_connect"))
    )
    (net (code "82") (name "unconnected-(U3B-DNU13-PadK8)") (class "Default")
      (node (ref "U3") (pin "K8") (pinfunction "DNU13_K8") (pintype "passive+no_connect"))
    )
    (net (code "83") (name "unconnected-(U3B-DNU14-PadN5)") (class "Default")
      (node (ref "U3") (pin "N5") (pinfunction "DNU14_N5") (pintype "passive+no_connect"))
    )
    (net (code "84") (name "unconnected-(U3B-DNU15-PadK5)") (class "Default")
      (node (ref "U3") (pin "K5") (pinfunction "DNU15_K5") (pintype "passive+no_connect"))
    )
    (net (code "85") (name "unconnected-(U3B-DNU16-PadG11)") (class "Default")
      (node (ref "U3") (pin "G11") (pinfunction "DNU16_G11") (pintype "passive+no_connect"))
    )
    (net (code "86") (name "unconnected-(U3B-DNU17-PadN8)") (class "Default")
      (node (ref "U3") (pin "N8") (pinfunction "DNU17_N8") (pintype "passive+no_connect"))
    )
  )
)
